# Muxes_and_ADC.net
KiCad netlist of a schematic drawn in Altium Designer
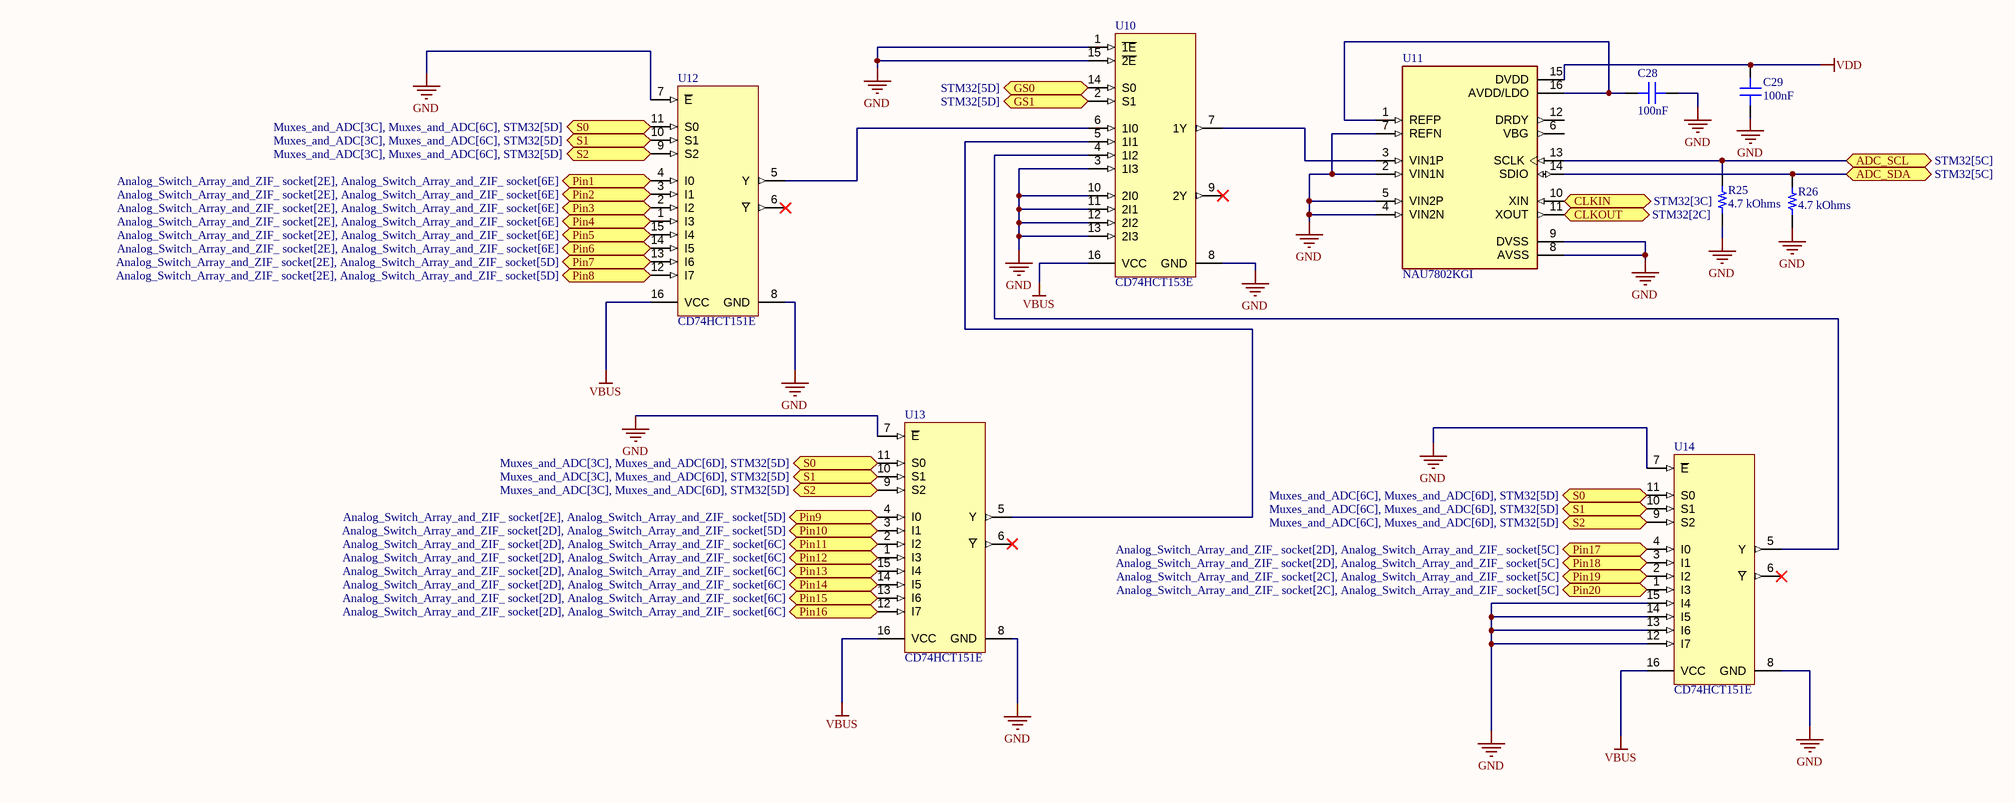
[diagram p0: Muxes_and_ADC.SchDoc]

(export (version "E")
  (design (tool "Eeschema 10.0.6"))
  (components
    (comp (ref "C28")
      (value "100nF")
      (footprint "CAP 1206_3216 - 0.8MM")
      (description "CAP CER 1206 0.1F 16V ULTRA STAB")
      (fields (field (name "PART NUMBER") "C1206X104G4HAC7800"))
      (libsource (lib "University of Massachusetts Lowell") (part "CAPACITOR"))
    )
    (comp (ref "C29")
      (value "100nF")
      (footprint "CAP 1206_3216 - 0.8MM")
      (description "CAP CER 1206 0.1F 16V ULTRA STAB")
      (fields (field (name "PART NUMBER") "C1206X104G4HAC7800"))
      (libsource (lib "University of Massachusetts Lowell") (part "CAPACITOR"))
    )
    (comp (ref "R25")
      (value "4.7 kOhms")
      (footprint "RES 0603_1608")
      (description "RES SMD 4.7K OHM 1% 1/10W 0603")
      (fields (field (name "PART NUMBER") "KTR03EZPF4701"))
      (libsource (lib "University of Massachusetts Lowell") (part "RESISTOR"))
    )
    (comp (ref "R26")
      (value "4.7 kOhms")
      (footprint "RES 0603_1608")
      (description "RES SMD 4.7K OHM 1% 1/10W 0603")
      (fields (field (name "PART NUMBER") "KTR03EZPF4701"))
      (libsource (lib "University of Massachusetts Lowell") (part "RESISTOR"))
    )
    (comp (ref "U10")
      (value "CD74HCT153E")
      (footprint "N0016A")
      (description "High Speed CMOS Logic Dual 4-Input Multiplexers, N0016A, TUBE")
      (fields
        (field (name "MANUFACTURER") "Texas Instruments")
        (field (name "GENERIC PART NUMBER") "CD74HCT153")
      )
      (libsource (lib "Altium Content Vault") (part "TI-CD54_74HCX153-16"))
    )
    (comp (ref "U11")
      (value "NAU7802KGI")
      (footprint "DIP792W45P254L1904H533Q16")
      (description "24 Bit Analog to Digital Converter 2 Input 1 Sigma-Delta 16-PDIP")
      (fields (field (name "MF") "Nuvoton Technology Corporation of America"))
      (libsource (lib "University of Massachusetts Lowell") (part "NAU7802KGI"))
    )
    (comp (ref "U12")
      (value "CD74HCT151E")
      (footprint "N0016A")
      (description "High Speed CMOS Logic 8-Input Multiplexer, N0016A, TUBE")
      (fields
        (field (name "MANUFACTURER") "Texas Instruments")
        (field (name "GENERIC PART NUMBER") "CD74HCT151")
      )
      (libsource (lib "Altium Content Vault") (part "TI-CDX4HCX151-16"))
    )
    (comp (ref "U13")
      (value "CD74HCT151E")
      (footprint "N0016A")
      (description "High Speed CMOS Logic 8-Input Multiplexer, N0016A, TUBE")
      (fields
        (field (name "MANUFACTURER") "Texas Instruments")
        (field (name "GENERIC PART NUMBER") "CD74HCT151")
      )
      (libsource (lib "Altium Content Vault") (part "TI-CDX4HCX151-16"))
    )
    (comp (ref "U14")
      (value "CD74HCT151E")
      (footprint "N0016A")
      (description "High Speed CMOS Logic 8-Input Multiplexer, N0016A, TUBE")
      (fields
        (field (name "MANUFACTURER") "Texas Instruments")
        (field (name "GENERIC PART NUMBER") "CD74HCT151")
      )
      (libsource (lib "Altium Content Vault") (part "TI-CDX4HCX151-16"))
    )
  )
  (nets
    (net (code "1") (name "/ADC_SCL") (class "Default")
      (node (ref "R25") (pin "2") (pinfunction "2_2") (pintype "passive"))
      (node (ref "U11") (pin "13") (pinfunction "SCLK_13") (pintype "input"))
    )
    (net (code "2") (name "/ADC_SDA") (class "Default")
      (node (ref "R26") (pin "2") (pinfunction "2_2") (pintype "passive"))
      (node (ref "U11") (pin "14") (pinfunction "SDIO_14") (pintype "bidirectional"))
    )
    (net (code "3") (name "/CLKIN") (class "Default")
      (node (ref "U11") (pin "10") (pinfunction "XIN_10") (pintype "input"))
    )
    (net (code "4") (name "/CLKOUT") (class "Default")
      (node (ref "U11") (pin "11") (pinfunction "XOUT_11") (pintype "output"))
    )
    (net (code "5") (name "/GS0") (class "Default")
      (node (ref "U10") (pin "14") (pinfunction "S0_14") (pintype "input"))
    )
    (net (code "6") (name "/GS1") (class "Default")
      (node (ref "U10") (pin "2") (pinfunction "S1_2") (pintype "input"))
    )
    (net (code "7") (name "/Pin1") (class "Default")
      (node (ref "U12") (pin "4") (pinfunction "I0_4") (pintype "input"))
    )
    (net (code "8") (name "/Pin2") (class "Default")
      (node (ref "U12") (pin "3") (pinfunction "I1_3") (pintype "input"))
    )
    (net (code "9") (name "/Pin3") (class "Default")
      (node (ref "U12") (pin "2") (pinfunction "I2_2") (pintype "input"))
    )
    (net (code "10") (name "/Pin4") (class "Default")
      (node (ref "U12") (pin "1") (pinfunction "I3_1") (pintype "input"))
    )
    (net (code "11") (name "/Pin5") (class "Default")
      (node (ref "U12") (pin "15") (pinfunction "I4_15") (pintype "input"))
    )
    (net (code "12") (name "/Pin6") (class "Default")
      (node (ref "U12") (pin "14") (pinfunction "I5_14") (pintype "input"))
    )
    (net (code "13") (name "/Pin7") (class "Default")
      (node (ref "U12") (pin "13") (pinfunction "I6_13") (pintype "input"))
    )
    (net (code "14") (name "/Pin8") (class "Default")
      (node (ref "U12") (pin "12") (pinfunction "I7_12") (pintype "input"))
    )
    (net (code "15") (name "/Pin9") (class "Default")
      (node (ref "U13") (pin "4") (pinfunction "I0_4") (pintype "input"))
    )
    (net (code "16") (name "/Pin10") (class "Default")
      (node (ref "U13") (pin "3") (pinfunction "I1_3") (pintype "input"))
    )
    (net (code "17") (name "/Pin11") (class "Default")
      (node (ref "U13") (pin "2") (pinfunction "I2_2") (pintype "input"))
    )
    (net (code "18") (name "/Pin12") (class "Default")
      (node (ref "U13") (pin "1") (pinfunction "I3_1") (pintype "input"))
    )
    (net (code "19") (name "/Pin13") (class "Default")
      (node (ref "U13") (pin "15") (pinfunction "I4_15") (pintype "input"))
    )
    (net (code "20") (name "/Pin14") (class "Default")
      (node (ref "U13") (pin "14") (pinfunction "I5_14") (pintype "input"))
    )
    (net (code "21") (name "/Pin15") (class "Default")
      (node (ref "U13") (pin "13") (pinfunction "I6_13") (pintype "input"))
    )
    (net (code "22") (name "/Pin16") (class "Default")
      (node (ref "U13") (pin "12") (pinfunction "I7_12") (pintype "input"))
    )
    (net (code "23") (name "/Pin17") (class "Default")
      (node (ref "U14") (pin "4") (pinfunction "I0_4") (pintype "input"))
    )
    (net (code "24") (name "/Pin18") (class "Default")
      (node (ref "U14") (pin "3") (pinfunction "I1_3") (pintype "input"))
    )
    (net (code "25") (name "/Pin19") (class "Default")
      (node (ref "U14") (pin "2") (pinfunction "I2_2") (pintype "input"))
    )
    (net (code "26") (name "/Pin20") (class "Default")
      (node (ref "U14") (pin "1") (pinfunction "I3_1") (pintype "input"))
    )
    (net (code "27") (name "/S0") (class "Default")
      (node (ref "U12") (pin "11") (pinfunction "S0_11") (pintype "input"))
      (node (ref "U13") (pin "11") (pinfunction "S0_11") (pintype "input"))
      (node (ref "U14") (pin "11") (pinfunction "S0_11") (pintype "input"))
    )
    (net (code "28") (name "/S1") (class "Default")
      (node (ref "U12") (pin "10") (pinfunction "S1_10") (pintype "input"))
      (node (ref "U13") (pin "10") (pinfunction "S1_10") (pintype "input"))
      (node (ref "U14") (pin "10") (pinfunction "S1_10") (pintype "input"))
    )
    (net (code "29") (name "/S2") (class "Default")
      (node (ref "U12") (pin "9") (pinfunction "S2_9") (pintype "input"))
      (node (ref "U13") (pin "9") (pinfunction "S2_9") (pintype "input"))
      (node (ref "U14") (pin "9") (pinfunction "S2_9") (pintype "input"))
    )
    (net (code "30") (name "GND") (class "Default")
      (node (ref "C28") (pin "1") (pinfunction "1_1") (pintype "passive"))
      (node (ref "C29") (pin "2") (pinfunction "2_2") (pintype "passive"))
      (node (ref "R25") (pin "1") (pinfunction "1_1") (pintype "passive"))
      (node (ref "R26") (pin "1") (pinfunction "1_1") (pintype "passive"))
      (node (ref "U10") (pin "1") (pinfunction "~{1E}_1") (pintype "input"))
      (node (ref "U10") (pin "10") (pinfunction "2I0_10") (pintype "input"))
      (node (ref "U10") (pin "11") (pinfunction "2I1_11") (pintype "input"))
      (node (ref "U10") (pin "12") (pinfunction "2I2_12") (pintype "input"))
      (node (ref "U10") (pin "13") (pinfunction "2I3_13") (pintype "input"))
      (node (ref "U10") (pin "15") (pinfunction "~{2E}_15") (pintype "input"))
      (node (ref "U10") (pin "3") (pinfunction "1I3_3") (pintype "input"))
      (node (ref "U10") (pin "8") (pinfunction "GND_8") (pintype "power_in"))
      (node (ref "U11") (pin "2") (pinfunction "VIN1N_2") (pintype "input"))
      (node (ref "U11") (pin "4") (pinfunction "VIN2N_4") (pintype "input"))
      (node (ref "U11") (pin "5") (pinfunction "VIN2P_5") (pintype "input"))
      (node (ref "U11") (pin "7") (pinfunction "REFN_7") (pintype "input"))
      (node (ref "U11") (pin "8") (pinfunction "AVSS_8") (pintype "power_in"))
      (node (ref "U11") (pin "9") (pinfunction "DVSS_9") (pintype "power_in"))
      (node (ref "U12") (pin "7") (pinfunction "~{E}_7") (pintype "input"))
      (node (ref "U12") (pin "8") (pinfunction "GND_8") (pintype "power_in"))
      (node (ref "U13") (pin "7") (pinfunction "~{E}_7") (pintype "input"))
      (node (ref "U13") (pin "8") (pinfunction "GND_8") (pintype "power_in"))
      (node (ref "U14") (pin "12") (pinfunction "I7_12") (pintype "input"))
      (node (ref "U14") (pin "13") (pinfunction "I6_13") (pintype "input"))
      (node (ref "U14") (pin "14") (pinfunction "I5_14") (pintype "input"))
      (node (ref "U14") (pin "15") (pinfunction "I4_15") (pintype "input"))
      (node (ref "U14") (pin "7") (pinfunction "~{E}_7") (pintype "input"))
      (node (ref "U14") (pin "8") (pinfunction "GND_8") (pintype "power_in"))
    )
    (net (code "31") (name "Net-(U10-1I0)") (class "Default")
      (node (ref "U10") (pin "6") (pinfunction "1I0_6") (pintype "input"))
      (node (ref "U12") (pin "5") (pinfunction "Y_5") (pintype "output"))
    )
    (net (code "32") (name "Net-(U10-1I1)") (class "Default")
      (node (ref "U10") (pin "5") (pinfunction "1I1_5") (pintype "input"))
      (node (ref "U13") (pin "5") (pinfunction "Y_5") (pintype "output"))
    )
    (net (code "33") (name "Net-(U10-1I2)") (class "Default")
      (node (ref "U10") (pin "4") (pinfunction "1I2_4") (pintype "input"))
      (node (ref "U14") (pin "5") (pinfunction "Y_5") (pintype "output"))
    )
    (net (code "34") (name "Net-(U10-1Y)") (class "Default")
      (node (ref "U10") (pin "7") (pinfunction "1Y_7") (pintype "output"))
      (node (ref "U11") (pin "3") (pinfunction "VIN1P_3") (pintype "input"))
    )
    (net (code "35") (name "Net-(U11-AVDD{slash}LDO)") (class "Default")
      (node (ref "C28") (pin "2") (pinfunction "2_2") (pintype "passive"))
      (node (ref "U11") (pin "1") (pinfunction "REFP_1") (pintype "input"))
      (node (ref "U11") (pin "16") (pinfunction "AVDD/LDO_16") (pintype "power_in"))
    )
    (net (code "36") (name "VBUS") (class "Default")
      (node (ref "U10") (pin "16") (pinfunction "VCC_16") (pintype "power_in"))
      (node (ref "U12") (pin "16") (pinfunction "VCC_16") (pintype "power_in"))
      (node (ref "U13") (pin "16") (pinfunction "VCC_16") (pintype "power_in"))
      (node (ref "U14") (pin "16") (pinfunction "VCC_16") (pintype "power_in"))
    )
    (net (code "37") (name "VDD") (class "Default")
      (node (ref "C29") (pin "1") (pinfunction "1_1") (pintype "passive"))
      (node (ref "U11") (pin "15") (pinfunction "DVDD_15") (pintype "power_in"))
    )
    (net (code "38") (name "unconnected-(U10-2Y-Pad9)") (class "Default")
      (node (ref "U10") (pin "9") (pinfunction "2Y_9") (pintype "output+no_connect"))
    )
    (net (code "39") (name "unconnected-(U11-DRDY-Pad12)") (class "Default")
      (node (ref "U11") (pin "12") (pinfunction "DRDY_12") (pintype "output"))
    )
    (net (code "40") (name "unconnected-(U11-VBG-Pad6)") (class "Default")
      (node (ref "U11") (pin "6") (pinfunction "VBG_6") (pintype "output"))
    )
    (net (code "41") (name "unconnected-(U12-~{Y}-Pad6)") (class "Default")
      (node (ref "U12") (pin "6") (pinfunction "~{Y}_6") (pintype "output+no_connect"))
    )
    (net (code "42") (name "unconnected-(U13-~{Y}-Pad6)") (class "Default")
      (node (ref "U13") (pin "6") (pinfunction "~{Y}_6") (pintype "output+no_connect"))
    )
    (net (code "43") (name "unconnected-(U14-~{Y}-Pad6)") (class "Default")
      (node (ref "U14") (pin "6") (pinfunction "~{Y}_6") (pintype "output+no_connect"))
    )
  )
)
